# main.net
KiCad netlist of a schematic drawn in Altium Designer
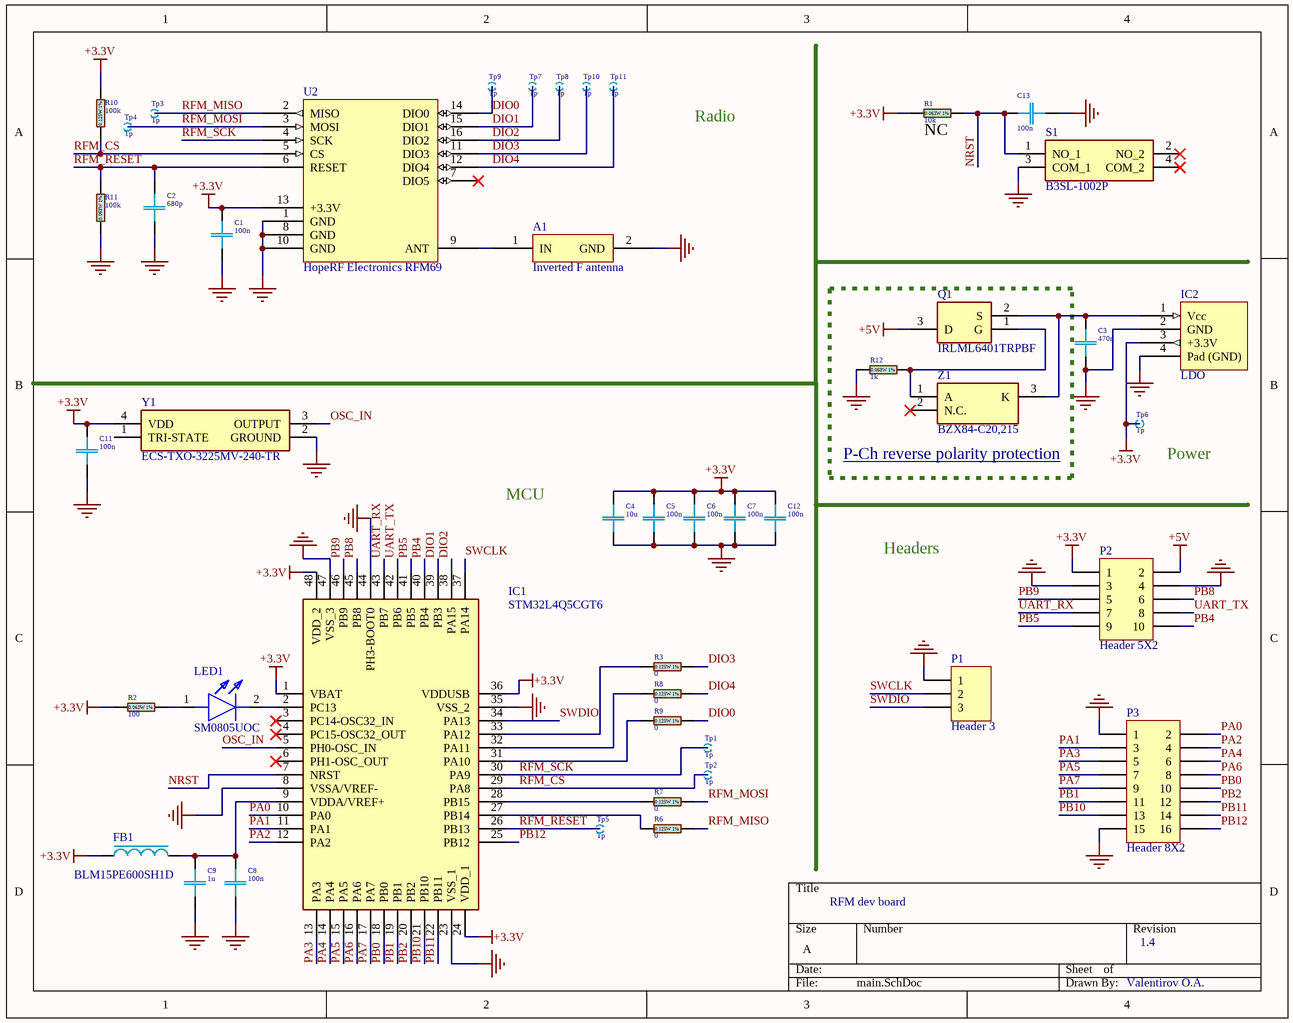
[diagram p0: main.SchDoc]

(export (version "E")
  (design (tool "Eeschema 10.0.6"))
  (components
    (comp (ref "A1")
      (value "Inverted F antenna")
      (footprint "Invertef_F-footprint")
      (libsource (lib "radio") (part "inverted_F"))
    )
    (comp (ref "C1")
      (value "100n")
      (footprint "C 0402(1005)x0.5")
      (description "SMD 0402     16V X5R 10%")
      (fields (field (name "MANUFACTURER") "Samsung") (field (name "PUBLISHER") "Hefest"))
      (libsource (lib "SMD Passive") (part "C 0402    16V X5R - 0*"))
    )
    (comp (ref "C2")
      (value "680p")
      (footprint "C 0402(1005)x0.5")
      (description "SMD 0402     16V X5R 10%")
      (fields (field (name "MANUFACTURER") "Samsung") (field (name "PUBLISHER") "Hefest"))
      (libsource (lib "SMD Passive") (part "C 0402    16V X5R - 0*"))
    )
    (comp (ref "C3")
      (value "470n")
      (footprint "C 0603(1608)x0.8")
      (description "SMD 0603     50V X7R   5%")
      (fields
        (field (name "PART NUMBER") "CL10B104JB8NNNC")
        (field (name "MANUFACTURER") "Samsung")
        (field (name "PUBLISHER") "Hefest")
      )
      (libsource (lib "SMD Passive") (part "C 0603    50V X7R - 100n"))
    )
    (comp (ref "C4")
      (value "10u")
      (footprint "C 0402(1005)x0.5")
      (description "SMD 0402     16V X5R 10%")
      (fields (field (name "MANUFACTURER") "Samsung") (field (name "PUBLISHER") "Hefest"))
      (libsource (lib "SMD Passive") (part "C 0402    16V X5R - 0*"))
    )
    (comp (ref "C5")
      (value "100n")
      (footprint "C 0402(1005)x0.5")
      (description "SMD 0402     16V X5R 10%")
      (fields (field (name "MANUFACTURER") "Samsung") (field (name "PUBLISHER") "Hefest"))
      (libsource (lib "SMD Passive") (part "C 0402    16V X5R - 0*"))
    )
    (comp (ref "C6")
      (value "100n")
      (footprint "C 0402(1005)x0.5")
      (description "SMD 0402     16V X5R 10%")
      (fields (field (name "MANUFACTURER") "Samsung") (field (name "PUBLISHER") "Hefest"))
      (libsource (lib "SMD Passive") (part "C 0402    16V X5R - 0*"))
    )
    (comp (ref "C7")
      (value "100n")
      (footprint "C 0402(1005)x0.5")
      (description "SMD 0402     16V X5R 10%")
      (fields (field (name "MANUFACTURER") "Samsung") (field (name "PUBLISHER") "Hefest"))
      (libsource (lib "SMD Passive") (part "C 0402    16V X5R - 0*"))
    )
    (comp (ref "C8")
      (value "100n")
      (footprint "C 0402(1005)x0.5")
      (description "SMD 0402     16V X5R 10%")
      (fields (field (name "MANUFACTURER") "Samsung") (field (name "PUBLISHER") "Hefest"))
      (libsource (lib "SMD Passive") (part "C 0402    16V X5R - 0*"))
    )
    (comp (ref "C9")
      (value "1u")
      (footprint "C 0402(1005)x0.5")
      (description "SMD 0402     16V X5R 10%")
      (fields (field (name "MANUFACTURER") "Samsung") (field (name "PUBLISHER") "Hefest"))
      (libsource (lib "SMD Passive") (part "C 0402    16V X5R - 0*"))
    )
    (comp (ref "C11")
      (value "100n")
      (footprint "C 0402(1005)x0.5")
      (description "SMD 0402     16V X5R 10%")
      (fields (field (name "MANUFACTURER") "Samsung") (field (name "PUBLISHER") "Hefest"))
      (libsource (lib "SMD Passive") (part "C 0402    16V X5R - 0*"))
    )
    (comp (ref "C12")
      (value "100n")
      (footprint "C 0402(1005)x0.5")
      (description "SMD 0402     16V X5R 10%")
      (fields (field (name "MANUFACTURER") "Samsung") (field (name "PUBLISHER") "Hefest"))
      (libsource (lib "SMD Passive") (part "C 0402    16V X5R - 0*"))
    )
    (comp (ref "C13")
      (value "100n")
      (footprint "C 0402(1005)x0.5")
      (description "SMD 0402     16V X5R 10%")
      (fields (field (name "MANUFACTURER") "Samsung") (field (name "PUBLISHER") "Hefest"))
      (libsource (lib "SMD Passive") (part "C 0402    16V X5R - 0*"))
    )
    (comp (ref "FB1")
      (value "BLM15PE600SH1D")
      (footprint "SamacSys:NFZ15SG152SN10B")
      (description "Ferrite Bead")
      (fields (field (name "MOUSER PART NUMBER") "81-BLM15PE600SH1D"))
      (libsource (lib "SamacSys") (part "BLM15PE600SH1D"))
    )
    (comp (ref "IC1")
      (value "STM32L4Q5CGT6")
      (footprint "SamacSys:QFP50P900X900X160-48N")
      (description "Integrated Circuit")
      (fields (field (name "MOUSER PART NUMBER") "511-STM32L4Q5CGT6"))
      (libsource (lib "SamacSys") (part "STM32L4Q5CGT6"))
    )
    (comp (ref "IC2")
      (value "LDO")
      (footprint "SOT230P700X180-4N")
      (description "LDO voltage regulator. In 4.5V - 5.5V. Out 3.3V")
      (libsource (lib "power") (part "LM3940IMP-3.3"))
    )
    (comp (ref "LED1")
      (value "SM0805UOC")
      (footprint "SamacSys:SM0805UOC")
      (description "LED")
      (fields (field (name "MOUSER PART NUMBER") "749-SM0805UOC"))
      (libsource (lib "SamacSys") (part "SM0805UOC"))
    )
    (comp (ref "P1")
      (value "Header 3")
      (footprint "HDR1X3")
      (description "Header, 3-Pin")
      (fields (field (name "PUBLISHER") "Altium Limited"))
      (libsource (lib "Miscellaneous Connectors") (part "Header 3"))
    )
    (comp (ref "P2")
      (value "Header 5X2")
      (footprint "HDR2X5")
      (description "Header, 5-Pin, Dual row")
      (fields (field (name "PUBLISHER") "Altium Limited"))
      (libsource (lib "Miscellaneous Connectors") (part "Header 5X2"))
    )
    (comp (ref "P3")
      (value "Header 8X2")
      (footprint "HDR2X8")
      (description "Header, 8-Pin, Dual row")
      (fields (field (name "PUBLISHER") "Altium Limited"))
      (libsource (lib "Miscellaneous Connectors") (part "Header 8X2"))
    )
    (comp (ref "Q1")
      (value "IRLML6401TRPBF")
      (footprint "SamacSys:SOT95P237X112-3N")
      (description "Transistor")
      (fields (field (name "MOUSER PART NUMBER") "942-IRLML6401TRPBF"))
      (libsource (lib "SamacSys") (part "IRLML6401TRPBF"))
    )
    (comp (ref "R1")
      (value "10k")
      (footprint "R 0402(1005)-1%")
      (description "SMD 0402 0.063W 1%   50V")
      (fields
        (field (name "MANUFACTURER") "YAGEO")
        (field (name "POWER") "0.0625W")
        (field (name "PUBLISHER") "Hefest")
      )
      (libsource (lib "SMD Passive") (part "R 0402-1%"))
    )
    (comp (ref "R2")
      (value "100")
      (footprint "R 0402(1005)-1%")
      (description "SMD 0402 0.063W 1%   50V")
      (fields
        (field (name "MANUFACTURER") "YAGEO")
        (field (name "POWER") "0.0625W")
        (field (name "PUBLISHER") "Hefest")
      )
      (libsource (lib "SMD Passive") (part "R 0402-1%"))
    )
    (comp (ref "R3")
      (value "0")
      (footprint "R 0805(2012)-1%")
      (description "SMD 0805 0.125W 1% 150V")
      (fields
        (field (name "MANUFACTURER") "YAGEO")
        (field (name "POWER") "0.125W")
        (field (name "PUBLISHER") "Hefest")
      )
      (libsource (lib "") (part "R 0805-1%_1"))
    )
    (comp (ref "R6")
      (value "0")
      (footprint "R 0805(2012)-1%")
      (description "SMD 0805 0.125W 1% 150V")
      (fields
        (field (name "MANUFACTURER") "YAGEO")
        (field (name "POWER") "0.125W")
        (field (name "PUBLISHER") "Hefest")
      )
      (libsource (lib "") (part "R 0805-1%_1"))
    )
    (comp (ref "R7")
      (value "0")
      (footprint "R 0805(2012)-1%")
      (description "SMD 0805 0.125W 1% 150V")
      (fields
        (field (name "MANUFACTURER") "YAGEO")
        (field (name "POWER") "0.125W")
        (field (name "PUBLISHER") "Hefest")
      )
      (libsource (lib "") (part "R 0805-1%_1"))
    )
    (comp (ref "R8")
      (value "0")
      (footprint "R 0805(2012)-1%")
      (description "SMD 0805 0.125W 1% 150V")
      (fields
        (field (name "MANUFACTURER") "YAGEO")
        (field (name "POWER") "0.125W")
        (field (name "PUBLISHER") "Hefest")
      )
      (libsource (lib "") (part "R 0805-1%_1"))
    )
    (comp (ref "R9")
      (value "0")
      (footprint "R 0805(2012)-1%")
      (description "SMD 0805 0.125W 1% 150V")
      (fields
        (field (name "MANUFACTURER") "YAGEO")
        (field (name "POWER") "0.125W")
        (field (name "PUBLISHER") "Hefest")
      )
      (libsource (lib "") (part "R 0805-1%_1"))
    )
    (comp (ref "R10")
      (value "100k")
      (footprint "R 0805(2012)-1%")
      (description "SMD 0805 0.125W 1% 150V")
      (fields
        (field (name "MANUFACTURER") "YAGEO")
        (field (name "POWER") "0.125W")
        (field (name "PUBLISHER") "Hefest")
      )
      (libsource (lib "SMD Passive") (part "R 0805-1%"))
    )
    (comp (ref "R11")
      (value "100k")
      (footprint "R 0402(1005)-1%")
      (description "SMD 0402 0.063W 1%   50V")
      (fields
        (field (name "MANUFACTURER") "YAGEO")
        (field (name "POWER") "0.0625W")
        (field (name "PUBLISHER") "Hefest")
      )
      (libsource (lib "") (part "R 0402-1%_1"))
    )
    (comp (ref "R12")
      (value "1k")
      (footprint "R 0402(1005)-1%")
      (description "SMD 0402 0.063W 1%   50V")
      (fields
        (field (name "MANUFACTURER") "YAGEO")
        (field (name "POWER") "0.0625W")
        (field (name "PUBLISHER") "Hefest")
      )
      (libsource (lib "SMD Passive") (part "R 0402-1%"))
    )
    (comp (ref "S1")
      (value "B3SL-1002P")
      (footprint "SamacSys:B3SL1002P")
      (description "Switch")
      (fields (field (name "MOUSER PART NUMBER") "653-B3SL-1002P"))
      (libsource (lib "SamacSys") (part "B3SL-1002P"))
    )
    (comp (ref "Tp1")
      (value "Tp")
      (footprint "Tp-0.5")
      (description "TestPoint")
      (fields (field (name "PUBLISHER") "Hefest"))
      (libsource (lib "SMD Passive") (part "Tp"))
    )
    (comp (ref "Tp2")
      (value "Tp")
      (footprint "Tp-0.5")
      (description "TestPoint")
      (fields (field (name "PUBLISHER") "Hefest"))
      (libsource (lib "SMD Passive") (part "Tp"))
    )
    (comp (ref "Tp3")
      (value "Tp")
      (footprint "Tp-0.5")
      (description "TestPoint")
      (fields (field (name "PUBLISHER") "Hefest"))
      (libsource (lib "SMD Passive") (part "Tp"))
    )
    (comp (ref "Tp4")
      (value "Tp")
      (footprint "Tp-0.5")
      (description "TestPoint")
      (fields (field (name "PUBLISHER") "Hefest"))
      (libsource (lib "SMD Passive") (part "Tp"))
    )
    (comp (ref "Tp5")
      (value "Tp")
      (footprint "Tp-0.5")
      (description "TestPoint")
      (fields (field (name "PUBLISHER") "Hefest"))
      (libsource (lib "SMD Passive") (part "Tp"))
    )
    (comp (ref "Tp6")
      (value "Tp")
      (footprint "Tp-0.5")
      (description "TestPoint")
      (fields (field (name "PUBLISHER") "Hefest"))
      (libsource (lib "SMD Passive") (part "Tp"))
    )
    (comp (ref "Tp7")
      (value "Tp")
      (footprint "Tp-0.5")
      (description "TestPoint")
      (fields (field (name "PUBLISHER") "Hefest"))
      (libsource (lib "SMD Passive") (part "Tp"))
    )
    (comp (ref "Tp8")
      (value "Tp")
      (footprint "Tp-0.5")
      (description "TestPoint")
      (fields (field (name "PUBLISHER") "Hefest"))
      (libsource (lib "SMD Passive") (part "Tp"))
    )
    (comp (ref "Tp9")
      (value "Tp")
      (footprint "Tp-0.5")
      (description "TestPoint")
      (fields (field (name "PUBLISHER") "Hefest"))
      (libsource (lib "SMD Passive") (part "Tp"))
    )
    (comp (ref "Tp10")
      (value "Tp")
      (footprint "Tp-0.5")
      (description "TestPoint")
      (fields (field (name "PUBLISHER") "Hefest"))
      (libsource (lib "SMD Passive") (part "Tp"))
    )
    (comp (ref "Tp11")
      (value "Tp")
      (footprint "Tp-0.5")
      (description "TestPoint")
      (fields (field (name "PUBLISHER") "Hefest"))
      (libsource (lib "SMD Passive") (part "Tp"))
    )
    (comp (ref "U2")
      (value "HopeRF Electronics RFM69")
      (footprint "CAC-200P1600X1600-16N")
      (libsource (lib "radio") (part "RFM69"))
    )
    (comp (ref "Y1")
      (value "ECS-TXO-3225MV-240-TR")
      (footprint "SamacSys:ECSTXO3225MV240TR")
      (description "Crystal or Oscillator")
      (fields (field (name "MOUSER PART NUMBER") "520-TXO-3225MV-240-T"))
      (libsource (lib "SamacSys") (part "ECS-TXO-3225MV-240-TR"))
    )
    (comp (ref "Z1")
      (value "BZX84-C20,215")
      (footprint "SamacSys:BZX84C20215")
      (description "Zener Diode")
      (fields (field (name "MOUSER PART NUMBER") "771-BZX84-C20-T/R"))
      (libsource (lib "SamacSys") (part "BZX84-C20,215"))
    )
  )
  (nets
    (net (code "1") (name "+3.3V") (class "Default")
      (node (ref "C1") (pin "1") (pinfunction "1_1") (pintype "passive"))
      (node (ref "C11") (pin "1") (pinfunction "1_1") (pintype "passive"))
      (node (ref "C12") (pin "1") (pinfunction "1_1") (pintype "passive"))
      (node (ref "C4") (pin "1") (pinfunction "1_1") (pintype "passive"))
      (node (ref "C5") (pin "1") (pinfunction "1_1") (pintype "passive"))
      (node (ref "C6") (pin "1") (pinfunction "1_1") (pintype "passive"))
      (node (ref "C7") (pin "1") (pinfunction "1_1") (pintype "passive"))
      (node (ref "FB1") (pin "1") (pinfunction "1_1") (pintype "passive"))
      (node (ref "IC1") (pin "1") (pinfunction "VBAT_1") (pintype "passive"))
      (node (ref "IC1") (pin "24") (pinfunction "VDD_1_24") (pintype "passive"))
      (node (ref "IC1") (pin "36") (pinfunction "VDDUSB_36") (pintype "passive"))
      (node (ref "IC1") (pin "48") (pinfunction "VDD_2_48") (pintype "passive"))
      (node (ref "IC2") (pin "3") (pinfunction "+3.3V_3") (pintype "output"))
      (node (ref "P2") (pin "1") (pinfunction "1_1") (pintype "passive"))
      (node (ref "R1") (pin "1") (pinfunction "1_1") (pintype "passive"))
      (node (ref "R10") (pin "2") (pinfunction "2_2") (pintype "passive"))
      (node (ref "R2") (pin "1") (pinfunction "1_1") (pintype "passive"))
      (node (ref "Tp6") (pin "1") (pinfunction "1_1") (pintype "passive"))
      (node (ref "U2") (pin "13") (pinfunction "+3.3V_13") (pintype "passive"))
      (node (ref "Y1") (pin "4") (pinfunction "VDD_4") (pintype "passive"))
    )
    (net (code "2") (name "+5V") (class "Default")
      (node (ref "P2") (pin "2") (pinfunction "2_2") (pintype "passive"))
      (node (ref "Q1") (pin "3") (pinfunction "D_3") (pintype "passive"))
    )
    (net (code "3") (name "/DIO0") (class "Default")
      (node (ref "R9") (pin "2") (pinfunction "2_2") (pintype "passive"))
      (node (ref "Tp9") (pin "1") (pinfunction "1_1") (pintype "passive"))
      (node (ref "U2") (pin "14") (pinfunction "DIO0_14") (pintype "bidirectional"))
    )
    (net (code "4") (name "/DIO1") (class "Default")
      (node (ref "IC1") (pin "39") (pinfunction "PB3_39") (pintype "passive"))
      (node (ref "Tp7") (pin "1") (pinfunction "1_1") (pintype "passive"))
      (node (ref "U2") (pin "15") (pinfunction "DIO1_15") (pintype "bidirectional"))
    )
    (net (code "5") (name "/DIO2") (class "Default")
      (node (ref "IC1") (pin "38") (pinfunction "PA15_38") (pintype "passive"))
      (node (ref "Tp8") (pin "1") (pinfunction "1_1") (pintype "passive"))
      (node (ref "U2") (pin "16") (pinfunction "DIO2_16") (pintype "bidirectional"))
    )
    (net (code "6") (name "/DIO3") (class "Default")
      (node (ref "R3") (pin "2") (pinfunction "2_2") (pintype "passive"))
      (node (ref "Tp10") (pin "1") (pinfunction "1_1") (pintype "passive"))
      (node (ref "U2") (pin "11") (pinfunction "DIO3_11") (pintype "bidirectional"))
    )
    (net (code "7") (name "/DIO4") (class "Default")
      (node (ref "R8") (pin "2") (pinfunction "2_2") (pintype "passive"))
      (node (ref "Tp11") (pin "1") (pinfunction "1_1") (pintype "passive"))
      (node (ref "U2") (pin "12") (pinfunction "DIO4_12") (pintype "bidirectional"))
    )
    (net (code "8") (name "/NRST") (class "Default")
      (node (ref "C13") (pin "1") (pinfunction "1_1") (pintype "passive"))
      (node (ref "IC1") (pin "7") (pinfunction "NRST_7") (pintype "passive"))
      (node (ref "R1") (pin "2") (pinfunction "2_2") (pintype "passive"))
      (node (ref "S1") (pin "1") (pinfunction "NO_1_1") (pintype "passive"))
    )
    (net (code "9") (name "/OSC_IN") (class "Default")
      (node (ref "IC1") (pin "5") (pinfunction "PH0-OSC_IN_5") (pintype "passive"))
      (node (ref "Y1") (pin "3") (pinfunction "OUTPUT_3") (pintype "passive"))
    )
    (net (code "10") (name "/PA0") (class "Default")
      (node (ref "IC1") (pin "10") (pinfunction "PA0_10") (pintype "passive"))
      (node (ref "P3") (pin "2") (pinfunction "2_2") (pintype "passive"))
    )
    (net (code "11") (name "/PA1") (class "Default")
      (node (ref "IC1") (pin "11") (pinfunction "PA1_11") (pintype "passive"))
      (node (ref "P3") (pin "3") (pinfunction "3_3") (pintype "passive"))
    )
    (net (code "12") (name "/PA2") (class "Default")
      (node (ref "IC1") (pin "12") (pinfunction "PA2_12") (pintype "passive"))
      (node (ref "P3") (pin "4") (pinfunction "4_4") (pintype "passive"))
    )
    (net (code "13") (name "/PA3") (class "Default")
      (node (ref "IC1") (pin "13") (pinfunction "PA3_13") (pintype "passive"))
      (node (ref "P3") (pin "5") (pinfunction "5_5") (pintype "passive"))
    )
    (net (code "14") (name "/PA4") (class "Default")
      (node (ref "IC1") (pin "14") (pinfunction "PA4_14") (pintype "passive"))
      (node (ref "P3") (pin "6") (pinfunction "6_6") (pintype "passive"))
    )
    (net (code "15") (name "/PA5") (class "Default")
      (node (ref "IC1") (pin "15") (pinfunction "PA5_15") (pintype "passive"))
      (node (ref "P3") (pin "7") (pinfunction "7_7") (pintype "passive"))
    )
    (net (code "16") (name "/PA6") (class "Default")
      (node (ref "IC1") (pin "16") (pinfunction "PA6_16") (pintype "passive"))
      (node (ref "P3") (pin "8") (pinfunction "8_8") (pintype "passive"))
    )
    (net (code "17") (name "/PA7") (class "Default")
      (node (ref "IC1") (pin "17") (pinfunction "PA7_17") (pintype "passive"))
      (node (ref "P3") (pin "9") (pinfunction "9_9") (pintype "passive"))
    )
    (net (code "18") (name "/PB0") (class "Default")
      (node (ref "IC1") (pin "18") (pinfunction "PB0_18") (pintype "passive"))
      (node (ref "P3") (pin "10") (pinfunction "10_10") (pintype "passive"))
    )
    (net (code "19") (name "/PB1") (class "Default")
      (node (ref "IC1") (pin "19") (pinfunction "PB1_19") (pintype "passive"))
      (node (ref "P3") (pin "11") (pinfunction "11_11") (pintype "passive"))
    )
    (net (code "20") (name "/PB2") (class "Default")
      (node (ref "IC1") (pin "20") (pinfunction "PB2_20") (pintype "passive"))
      (node (ref "P3") (pin "12") (pinfunction "12_12") (pintype "passive"))
    )
    (net (code "21") (name "/PB4") (class "Default")
      (node (ref "IC1") (pin "40") (pinfunction "PB4_40") (pintype "passive"))
      (node (ref "P2") (pin "10") (pinfunction "10_10") (pintype "passive"))
    )
    (net (code "22") (name "/PB5") (class "Default")
      (node (ref "IC1") (pin "41") (pinfunction "PB5_41") (pintype "passive"))
      (node (ref "P2") (pin "9") (pinfunction "9_9") (pintype "passive"))
    )
    (net (code "23") (name "/PB8") (class "Default")
      (node (ref "IC1") (pin "45") (pinfunction "PB8_45") (pintype "passive"))
      (node (ref "P2") (pin "6") (pinfunction "6_6") (pintype "passive"))
    )
    (net (code "24") (name "/PB9") (class "Default")
      (node (ref "IC1") (pin "46") (pinfunction "PB9_46") (pintype "passive"))
      (node (ref "P2") (pin "5") (pinfunction "5_5") (pintype "passive"))
    )
    (net (code "25") (name "/PB10") (class "Default")
      (node (ref "IC1") (pin "21") (pinfunction "PB10_21") (pintype "passive"))
      (node (ref "P3") (pin "13") (pinfunction "13_13") (pintype "passive"))
    )
    (net (code "26") (name "/PB11") (class "Default")
      (node (ref "IC1") (pin "22") (pinfunction "PB11_22") (pintype "passive"))
      (node (ref "P3") (pin "14") (pinfunction "14_14") (pintype "passive"))
    )
    (net (code "27") (name "/PB12") (class "Default")
      (node (ref "IC1") (pin "25") (pinfunction "PB12_25") (pintype "passive"))
      (node (ref "P3") (pin "16") (pinfunction "16_16") (pintype "passive"))
    )
    (net (code "28") (name "/RFM_CS") (class "Default")
      (node (ref "IC1") (pin "29") (pinfunction "PA8_29") (pintype "passive"))
      (node (ref "R10") (pin "1") (pinfunction "1_1") (pintype "passive"))
      (node (ref "Tp2") (pin "1") (pinfunction "1_1") (pintype "passive"))
      (node (ref "U2") (pin "5") (pinfunction "CS_5") (pintype "input"))
    )
    (net (code "29") (name "/RFM_MISO") (class "Default")
      (node (ref "R6") (pin "2") (pinfunction "2_2") (pintype "passive"))
      (node (ref "Tp3") (pin "1") (pinfunction "1_1") (pintype "passive"))
      (node (ref "U2") (pin "2") (pinfunction "MISO_2") (pintype "output"))
    )
    (net (code "30") (name "/RFM_MOSI") (class "Default")
      (node (ref "R7") (pin "2") (pinfunction "2_2") (pintype "passive"))
      (node (ref "Tp4") (pin "1") (pinfunction "1_1") (pintype "passive"))
      (node (ref "U2") (pin "3") (pinfunction "MOSI_3") (pintype "input"))
    )
    (net (code "31") (name "/RFM_RESET") (class "Default")
      (node (ref "C2") (pin "1") (pinfunction "1_1") (pintype "passive"))
      (node (ref "IC1") (pin "26") (pinfunction "PB13_26") (pintype "passive"))
      (node (ref "R11") (pin "2") (pinfunction "2_2") (pintype "passive"))
      (node (ref "Tp5") (pin "1") (pinfunction "1_1") (pintype "passive"))
      (node (ref "U2") (pin "6") (pinfunction "RESET_6") (pintype "passive"))
    )
    (net (code "32") (name "/RFM_SCK") (class "Default")
      (node (ref "IC1") (pin "30") (pinfunction "PA9_30") (pintype "passive"))
      (node (ref "Tp1") (pin "1") (pinfunction "1_1") (pintype "passive"))
      (node (ref "U2") (pin "4") (pinfunction "SCK_4") (pintype "input"))
    )
    (net (code "33") (name "/SWCLK") (class "Default")
      (node (ref "IC1") (pin "37") (pinfunction "PA14_37") (pintype "passive"))
      (node (ref "P1") (pin "2") (pinfunction "2_2") (pintype "passive"))
    )
    (net (code "34") (name "/SWDIO") (class "Default")
      (node (ref "IC1") (pin "34") (pinfunction "PA13_34") (pintype "passive"))
      (node (ref "P1") (pin "3") (pinfunction "3_3") (pintype "passive"))
    )
    (net (code "35") (name "/UART_RX") (class "Default")
      (node (ref "IC1") (pin "43") (pinfunction "PB7_43") (pintype "passive"))
      (node (ref "P2") (pin "7") (pinfunction "7_7") (pintype "passive"))
    )
    (net (code "36") (name "/UART_TX") (class "Default")
      (node (ref "IC1") (pin "42") (pinfunction "PB6_42") (pintype "passive"))
      (node (ref "P2") (pin "8") (pinfunction "8_8") (pintype "passive"))
    )
    (net (code "37") (name "GND") (class "Default")
      (node (ref "A1") (pin "2") (pinfunction "GND_2") (pintype "passive"))
      (node (ref "C1") (pin "2") (pinfunction "2_2") (pintype "passive"))
      (node (ref "C11") (pin "2") (pinfunction "2_2") (pintype "passive"))
      (node (ref "C12") (pin "2") (pinfunction "2_2") (pintype "passive"))
      (node (ref "C13") (pin "2") (pinfunction "2_2") (pintype "passive"))
      (node (ref "C2") (pin "2") (pinfunction "2_2") (pintype "passive"))
      (node (ref "C3") (pin "2") (pinfunction "2_2") (pintype "passive"))
      (node (ref "C4") (pin "2") (pinfunction "2_2") (pintype "passive"))
      (node (ref "C5") (pin "2") (pinfunction "2_2") (pintype "passive"))
      (node (ref "C6") (pin "2") (pinfunction "2_2") (pintype "passive"))
      (node (ref "C7") (pin "2") (pinfunction "2_2") (pintype "passive"))
      (node (ref "C8") (pin "2") (pinfunction "2_2") (pintype "passive"))
      (node (ref "C9") (pin "2") (pinfunction "2_2") (pintype "passive"))
      (node (ref "IC1") (pin "23") (pinfunction "VSS_1_23") (pintype "passive"))
      (node (ref "IC1") (pin "35") (pinfunction "VSS_2_35") (pintype "passive"))
      (node (ref "IC1") (pin "44") (pinfunction "PH3-BOOT0_44") (pintype "passive"))
      (node (ref "IC1") (pin "47") (pinfunction "VSS_3_47") (pintype "passive"))
      (node (ref "IC1") (pin "8") (pinfunction "VSSA/VREF-_8") (pintype "passive"))
      (node (ref "IC2") (pin "2") (pinfunction "GND_2") (pintype "passive"))
      (node (ref "IC2") (pin "4") (pinfunction "Pad_(GND)_4") (pintype "passive"))
      (node (ref "P1") (pin "1") (pinfunction "1_1") (pintype "passive"))
      (node (ref "P2") (pin "3") (pinfunction "3_3") (pintype "passive"))
      (node (ref "P2") (pin "4") (pinfunction "4_4") (pintype "passive"))
      (node (ref "P3") (pin "1") (pinfunction "1_1") (pintype "passive"))
      (node (ref "P3") (pin "15") (pinfunction "15_15") (pintype "passive"))
      (node (ref "R11") (pin "1") (pinfunction "1_1") (pintype "passive"))
      (node (ref "R12") (pin "1") (pinfunction "1_1") (pintype "passive"))
      (node (ref "S1") (pin "3") (pinfunction "COM_1_3") (pintype "passive"))
      (node (ref "U2") (pin "1") (pinfunction "GND_1") (pintype "passive"))
      (node (ref "U2") (pin "10") (pinfunction "GND_10") (pintype "passive"))
      (node (ref "U2") (pin "8") (pinfunction "GND_8") (pintype "passive"))
      (node (ref "Y1") (pin "2") (pinfunction "GROUND_2") (pintype "passive"))
    )
    (net (code "38") (name "Net-(A1-IN)") (class "Default")
      (node (ref "A1") (pin "1") (pinfunction "IN_1") (pintype "passive"))
      (node (ref "U2") (pin "9") (pinfunction "ANT_9") (pintype "passive"))
    )
    (net (code "39") (name "Net-(IC1-PA10)") (class "Default")
      (node (ref "IC1") (pin "31") (pinfunction "PA10_31") (pintype "passive"))
      (node (ref "R9") (pin "1") (pinfunction "1_1") (pintype "passive"))
    )
    (net (code "40") (name "Net-(IC1-PA11)") (class "Default")
      (node (ref "IC1") (pin "32") (pinfunction "PA11_32") (pintype "passive"))
      (node (ref "R8") (pin "1") (pinfunction "1_1") (pintype "passive"))
    )
    (net (code "41") (name "Net-(IC1-PA12)") (class "Default")
      (node (ref "IC1") (pin "33") (pinfunction "PA12_33") (pintype "passive"))
      (node (ref "R3") (pin "1") (pinfunction "1_1") (pintype "passive"))
    )
    (net (code "42") (name "Net-(IC1-PB14)") (class "Default")
      (node (ref "IC1") (pin "27") (pinfunction "PB14_27") (pintype "passive"))
      (node (ref "R6") (pin "1") (pinfunction "1_1") (pintype "passive"))
    )
    (net (code "43") (name "Net-(IC1-PB15)") (class "Default")
      (node (ref "IC1") (pin "28") (pinfunction "PB15_28") (pintype "passive"))
      (node (ref "R7") (pin "1") (pinfunction "1_1") (pintype "passive"))
    )
    (net (code "44") (name "Net-(IC1-PC13)") (class "Default")
      (node (ref "IC1") (pin "2") (pinfunction "PC13_2") (pintype "passive"))
      (node (ref "LED1") (pin "2") (pinfunction "K_2") (pintype "passive"))
    )
    (net (code "45") (name "Net-(IC1-VDDA{slash}VREF+)") (class "Default")
      (node (ref "C8") (pin "1") (pinfunction "1_1") (pintype "passive"))
      (node (ref "C9") (pin "1") (pinfunction "1_1") (pintype "passive"))
      (node (ref "FB1") (pin "2") (pinfunction "2_2") (pintype "passive"))
      (node (ref "IC1") (pin "9") (pinfunction "VDDA/VREF+_9") (pintype "passive"))
    )
    (net (code "46") (name "Net-(IC2-Vcc)") (class "Default")
      (node (ref "C3") (pin "1") (pinfunction "1_1") (pintype "passive"))
      (node (ref "IC2") (pin "1") (pinfunction "Vcc_1") (pintype "input"))
      (node (ref "Q1") (pin "2") (pinfunction "S_2") (pintype "passive"))
      (node (ref "Z1") (pin "3") (pinfunction "K_3") (pintype "passive"))
    )
    (net (code "47") (name "Net-(LED1-A)") (class "Default")
      (node (ref "LED1") (pin "1") (pinfunction "A_1") (pintype "passive"))
      (node (ref "R2") (pin "2") (pinfunction "2_2") (pintype "passive"))
    )
    (net (code "48") (name "Net-(Q1-G)") (class "Default")
      (node (ref "Q1") (pin "1") (pinfunction "G_1") (pintype "passive"))
      (node (ref "R12") (pin "2") (pinfunction "2_2") (pintype "passive"))
      (node (ref "Z1") (pin "1") (pinfunction "A_1") (pintype "passive"))
    )
    (net (code "49") (name "unconnected-(IC1-PC14-OSC32_IN-Pad3)") (class "Default")
      (node (ref "IC1") (pin "3") (pinfunction "PC14-OSC32_IN_3") (pintype "passive+no_connect"))
    )
    (net (code "50") (name "unconnected-(IC1-PC15-OSC32_OUT-Pad4)") (class "Default")
      (node (ref "IC1") (pin "4") (pinfunction "PC15-OSC32_OUT_4") (pintype "passive+no_connect"))
    )
    (net (code "51") (name "unconnected-(IC1-PH1-OSC_OUT-Pad6)") (class "Default")
      (node (ref "IC1") (pin "6") (pinfunction "PH1-OSC_OUT_6") (pintype "passive+no_connect"))
    )
    (net (code "52") (name "unconnected-(S1-COM_2-Pad4)") (class "Default")
      (node (ref "S1") (pin "4") (pinfunction "COM_2_4") (pintype "passive+no_connect"))
    )
    (net (code "53") (name "unconnected-(S1-NO_2-Pad2)") (class "Default")
      (node (ref "S1") (pin "2") (pinfunction "NO_2_2") (pintype "passive+no_connect"))
    )
    (net (code "54") (name "unconnected-(U2-DIO5-Pad7)") (class "Default")
      (node (ref "U2") (pin "7") (pinfunction "DIO5_7") (pintype "bidirectional+no_connect"))
    )
    (net (code "55") (name "unconnected-(Y1-TRI-STATE-Pad1)") (class "Default")
      (node (ref "Y1") (pin "1") (pinfunction "TRI-STATE_1") (pintype "passive"))
    )
    (net (code "56") (name "unconnected-(Z1-N.C.-Pad2)") (class "Default")
      (node (ref "Z1") (pin "2") (pinfunction "N.C._2") (pintype "passive+no_connect"))
    )
  )
)
